# design.net
KiCad netlist of a schematic drawn in EasyEDA Pro
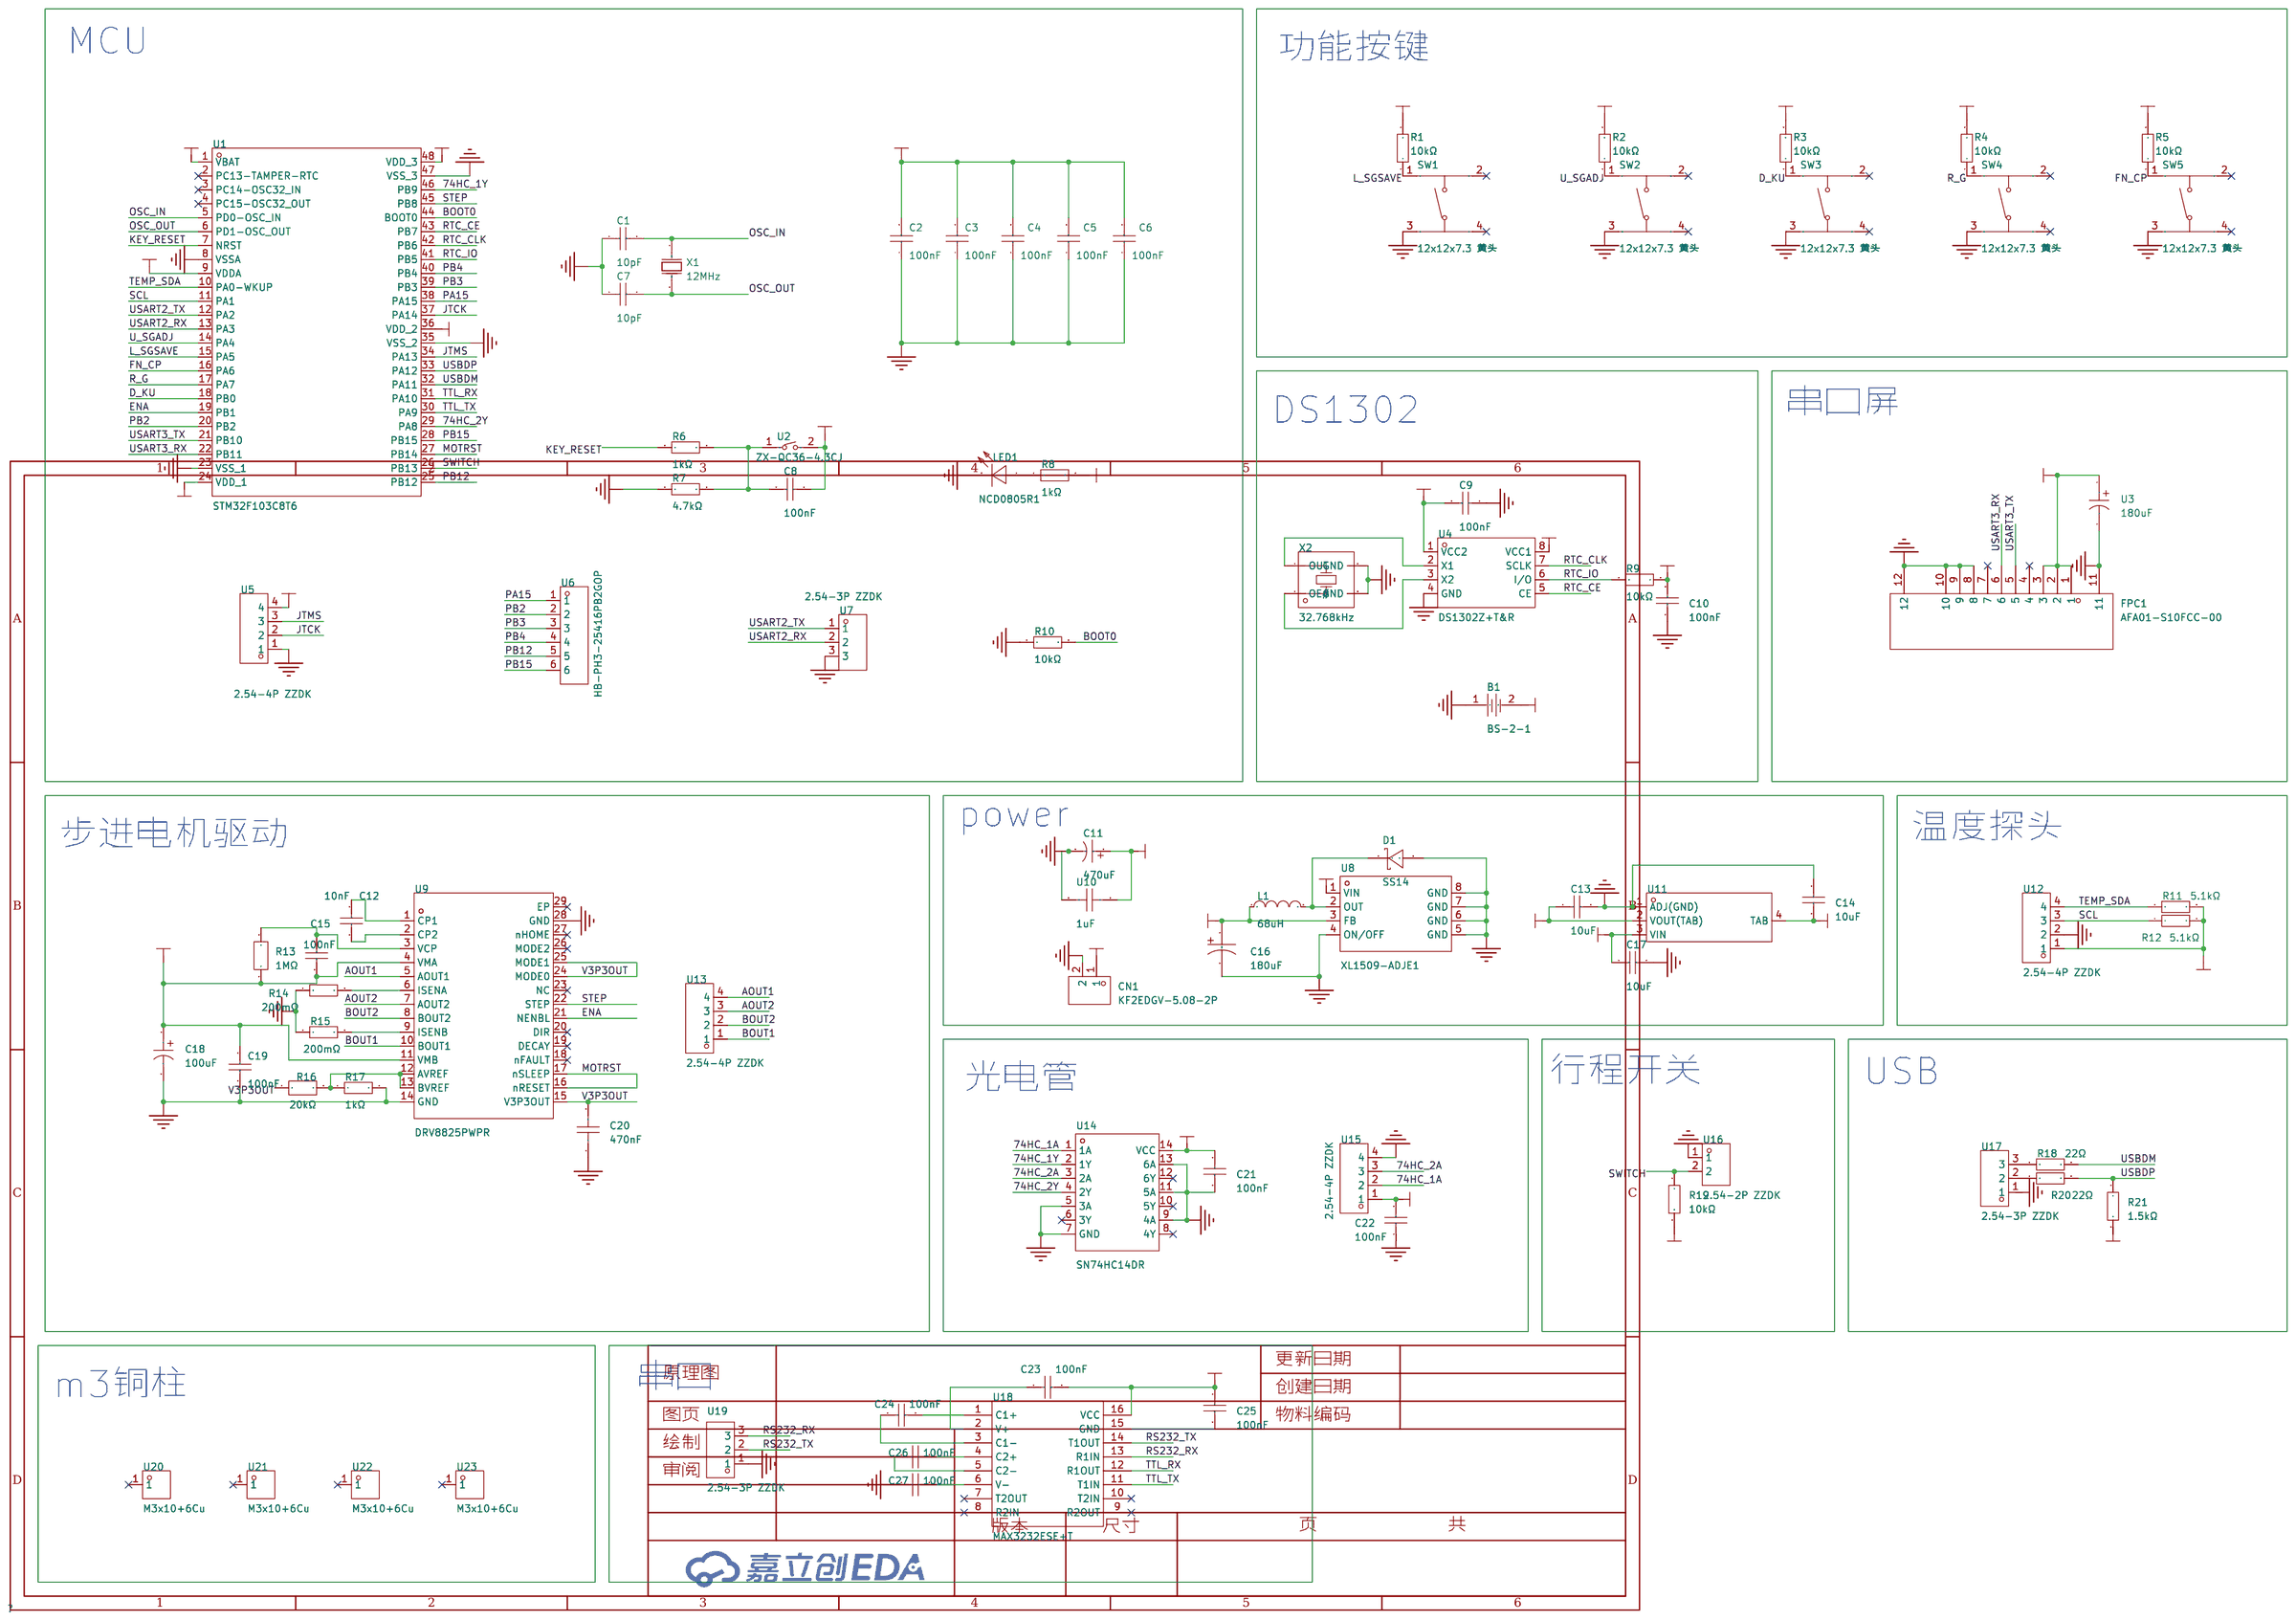
[diagram p0: schematic sheet]

(export (version "E")
  (design (tool "Eeschema 10.0.6"))
  (components
    (comp (ref "B1")
      (value "BS-2-1")
      (footprint "easyedapro:BAT-TH_BS-2-1")
      (description "连接器类型:电池底座;适用电池规格:-;工作温度范围:-55°C~+85°C;")
      (fields (field (name "Manufacturer") "Q&J"))
      (libsource (lib "easyedapro") (part "CR2032-BS-2-1"))
    )
    (comp (ref "C1")
      (value "10pF")
      (footprint "easyedapro:C0603")
      (description "容值:10pF;精度:±5%;额定电压:50V;材质(温度系数):C0G;")
      (fields
        (field (name "Manufacturer Part") "CL10C100JB8NNNC")
        (field (name "Manufacturer") "SAMSUNG(三星)")
      )
      (libsource (lib "easyedapro") (part "CL10C100JB8NNNC"))
    )
    (comp (ref "C2")
      (value "100nF")
      (footprint "easyedapro:C0805")
      (description "容值:100nF;精度:±10%;额定电压:50V;材质(温度系数):X7R;")
      (fields
        (field (name "Manufacturer Part") "CL21B104KBCNNNC")
        (field (name "Manufacturer") "SAMSUNG(三星)")
      )
      (libsource (lib "easyedapro") (part "CL21B104KBCNNNC"))
    )
    (comp (ref "C3")
      (value "100nF")
      (footprint "easyedapro:C0805")
      (description "容值:100nF;精度:±10%;额定电压:50V;材质(温度系数):X7R;")
      (fields
        (field (name "Manufacturer Part") "CL21B104KBCNNNC")
        (field (name "Manufacturer") "SAMSUNG(三星)")
      )
      (libsource (lib "easyedapro") (part "CL21B104KBCNNNC"))
    )
    (comp (ref "C4")
      (value "100nF")
      (footprint "easyedapro:C0805")
      (description "容值:100nF;精度:±10%;额定电压:50V;材质(温度系数):X7R;")
      (fields
        (field (name "Manufacturer Part") "CL21B104KBCNNNC")
        (field (name "Manufacturer") "SAMSUNG(三星)")
      )
      (libsource (lib "easyedapro") (part "CL21B104KBCNNNC"))
    )
    (comp (ref "C5")
      (value "100nF")
      (footprint "easyedapro:C0805")
      (description "容值:100nF;精度:±10%;额定电压:50V;材质(温度系数):X7R;")
      (fields
        (field (name "Manufacturer Part") "CL21B104KBCNNNC")
        (field (name "Manufacturer") "SAMSUNG(三星)")
      )
      (libsource (lib "easyedapro") (part "CL21B104KBCNNNC"))
    )
    (comp (ref "C6")
      (value "100nF")
      (footprint "easyedapro:C0805")
      (description "容值:100nF;精度:±10%;额定电压:50V;材质(温度系数):X7R;")
      (fields
        (field (name "Manufacturer Part") "CL21B104KBCNNNC")
        (field (name "Manufacturer") "SAMSUNG(三星)")
      )
      (libsource (lib "easyedapro") (part "CL21B104KBCNNNC"))
    )
    (comp (ref "C7")
      (value "10pF")
      (footprint "easyedapro:C0603")
      (description "容值:10pF;精度:±5%;额定电压:50V;材质(温度系数):C0G;")
      (fields
        (field (name "Manufacturer Part") "CL10C100JB8NNNC")
        (field (name "Manufacturer") "SAMSUNG(三星)")
      )
      (libsource (lib "easyedapro") (part "CL10C100JB8NNNC"))
    )
    (comp (ref "C8")
      (value "100nF")
      (footprint "easyedapro:C0805")
      (description "容值:100nF;精度:±10%;额定电压:50V;材质(温度系数):X7R;")
      (fields
        (field (name "Manufacturer Part") "CL21B104KBCNNNC")
        (field (name "Manufacturer") "SAMSUNG(三星)")
      )
      (libsource (lib "easyedapro") (part "CL21B104KBCNNNC"))
    )
    (comp (ref "C9")
      (value "100nF")
      (footprint "easyedapro:C0805")
      (description "容值:100nF;精度:±10%;额定电压:50V;材质(温度系数):X7R;")
      (fields
        (field (name "Manufacturer Part") "CL21B104KBCNNNC")
        (field (name "Manufacturer") "SAMSUNG(三星)")
      )
      (libsource (lib "easyedapro") (part "CL21B104KBCNNNC"))
    )
    (comp (ref "C10")
      (value "100nF")
      (footprint "easyedapro:C0805")
      (description "容值:100nF;精度:±10%;额定电压:50V;材质(温度系数):X7R;")
      (fields
        (field (name "Manufacturer Part") "CL21B104KBCNNNC")
        (field (name "Manufacturer") "SAMSUNG(三星)")
      )
      (libsource (lib "easyedapro") (part "CL21B104KBCNNNC"))
    )
    (comp (ref "C11")
      (value "470uF")
      (footprint "easyedapro:CAP-SMD_BD10.0-L10.3-W10.3-LS11.0-R-RD")
      (description "容值:470uF;精度:±20%;额定电压:35V;纹波电流:286mA@120Hz;等效串联电阻:-;")
      (fields (field (name "Manufacturer Part") "RVT1V471M1010") (field (name "Manufacturer") "ROQANG(容强)"))
      (libsource (lib "easyedapro") (part "RVT1V471M1010-C72519"))
    )
    (comp (ref "C12")
      (value "10nF")
      (footprint "easyedapro:C0805")
      (description "容值:10nF;精度:±10%;额定电压:50V;材质(温度系数):X7R;")
      (fields
        (field (name "Manufacturer Part") "CL21B103KBANNNC")
        (field (name "Manufacturer") "SAMSUNG(三星)")
      )
      (libsource (lib "easyedapro") (part "CL21B103KBANNNC"))
    )
    (comp (ref "C13")
      (value "10uF")
      (footprint "easyedapro:C0805")
      (description "容值:10uF;精度:±10%;额定电压:16V;材质(温度系数):X5R;")
      (fields
        (field (name "Manufacturer Part") "CL21A106KOQNNNE")
        (field (name "Manufacturer") "SAMSUNG(三星)")
      )
      (libsource (lib "easyedapro") (part "CL21A106KOQNNNE"))
    )
    (comp (ref "C14")
      (value "10uF")
      (footprint "easyedapro:C0805")
      (description "容值:10uF;精度:±10%;额定电压:16V;材质(温度系数):X5R;")
      (fields
        (field (name "Manufacturer Part") "CL21A106KOQNNNE")
        (field (name "Manufacturer") "SAMSUNG(三星)")
      )
      (libsource (lib "easyedapro") (part "CL21A106KOQNNNE"))
    )
    (comp (ref "C15")
      (value "100nF")
      (footprint "easyedapro:C0805")
      (description "容值:100nF;精度:±10%;额定电压:50V;材质(温度系数):X7R;")
      (fields
        (field (name "Manufacturer Part") "CL21B104KBCNNNC")
        (field (name "Manufacturer") "SAMSUNG(三星)")
      )
      (libsource (lib "easyedapro") (part "CL21B104KBCNNNC"))
    )
    (comp (ref "C16")
      (value "180uF")
      (footprint "easyedapro:CAP-TH_BD8.0-P3.50-D0.6-FD")
      (description "容值:180uF;精度:±20%;额定电压:35V;纹波电流:900mA@100kHz;等效串联电阻:210mΩ@100kHz;")
      (fields (field (name "Manufacturer Part") "LKMD0901V181MF") (field (name "Manufacturer") "Ymin(永铭)"))
      (libsource (lib "easyedapro") (part "LKMD0901V181MF"))
    )
    (comp (ref "C17")
      (value "10uF")
      (footprint "easyedapro:C0805")
      (description "容值:10uF;精度:±10%;额定电压:16V;材质(温度系数):X5R;")
      (fields
        (field (name "Manufacturer Part") "CL21A106KOQNNNE")
        (field (name "Manufacturer") "SAMSUNG(三星)")
      )
      (libsource (lib "easyedapro") (part "CL21A106KOQNNNE"))
    )
    (comp (ref "C18")
      (value "100uF")
      (footprint "easyedapro:CAP-SMD_BD6.3-L6.6-W6.6-LS7.6-FD-1")
      (description "容值:100uF;精度:±20%;额定电压:35V;纹波电流:230mA@120Hz;等效串联电阻:600mΩ@100kHz;")
      (fields
        (field (name "Manufacturer Part") "RVE100UF35V67RV0072")
        (field (name "Manufacturer") "KNSCHA(科尼盛)")
      )
      (libsource (lib "easyedapro") (part "RVE100UF35V67RV0072"))
    )
    (comp (ref "C19")
      (value "100nF")
      (footprint "easyedapro:C0805")
      (description "容值:100nF;精度:±10%;额定电压:50V;材质(温度系数):X7R;")
      (fields
        (field (name "Manufacturer Part") "CL21B104KBCNNNC")
        (field (name "Manufacturer") "SAMSUNG(三星)")
      )
      (libsource (lib "easyedapro") (part "CL21B104KBCNNNC"))
    )
    (comp (ref "C20")
      (value "470nF")
      (footprint "easyedapro:CAP-TH_L18.0-W8.5-P15.00-D0.8")
      (description "容值:470nF;精度:±10%;电压(AC):275V；310V；305V;等级:X2;")
      (fields
        (field (name "Manufacturer Part") "MPX474K31D4KN15800")
        (field (name "Manufacturer") "KNSCHA(科尼盛)")
      )
      (libsource (lib "easyedapro") (part "MPX474K31D4KN15800"))
    )
    (comp (ref "C21")
      (value "100nF")
      (footprint "easyedapro:C0805")
      (description "容值:100nF;精度:±10%;额定电压:50V;材质(温度系数):X7R;")
      (fields
        (field (name "Manufacturer Part") "CL21B104KBCNNNC")
        (field (name "Manufacturer") "SAMSUNG(三星)")
      )
      (libsource (lib "easyedapro") (part "CL21B104KBCNNNC"))
    )
    (comp (ref "C22")
      (value "100nF")
      (footprint "easyedapro:C0805")
      (description "容值:100nF;精度:±10%;额定电压:50V;材质(温度系数):X7R;")
      (fields
        (field (name "Manufacturer Part") "CL21B104KBCNNNC")
        (field (name "Manufacturer") "SAMSUNG(三星)")
      )
      (libsource (lib "easyedapro") (part "CL21B104KBCNNNC"))
    )
    (comp (ref "C23")
      (value "100nF")
      (footprint "easyedapro:C0805")
      (description "容值:100nF;精度:±10%;额定电压:50V;材质(温度系数):X7R;")
      (fields
        (field (name "Manufacturer Part") "CL21B104KBCNNNC")
        (field (name "Manufacturer") "SAMSUNG(三星)")
      )
      (libsource (lib "easyedapro") (part "CL21B104KBCNNNC"))
    )
    (comp (ref "C24")
      (value "100nF")
      (footprint "easyedapro:C0805")
      (description "容值:100nF;精度:±10%;额定电压:50V;材质(温度系数):X7R;")
      (fields
        (field (name "Manufacturer Part") "CL21B104KBCNNNC")
        (field (name "Manufacturer") "SAMSUNG(三星)")
      )
      (libsource (lib "easyedapro") (part "CL21B104KBCNNNC"))
    )
    (comp (ref "C25")
      (value "100nF")
      (footprint "easyedapro:C0805")
      (description "容值:100nF;精度:±10%;额定电压:50V;材质(温度系数):X7R;")
      (fields
        (field (name "Manufacturer Part") "CL21B104KBCNNNC")
        (field (name "Manufacturer") "SAMSUNG(三星)")
      )
      (libsource (lib "easyedapro") (part "CL21B104KBCNNNC"))
    )
    (comp (ref "C26")
      (value "100nF")
      (footprint "easyedapro:C0805")
      (description "容值:100nF;精度:±10%;额定电压:50V;材质(温度系数):X7R;")
      (fields
        (field (name "Manufacturer Part") "CL21B104KBCNNNC")
        (field (name "Manufacturer") "SAMSUNG(三星)")
      )
      (libsource (lib "easyedapro") (part "CL21B104KBCNNNC"))
    )
    (comp (ref "C27")
      (value "100nF")
      (footprint "easyedapro:C0805")
      (description "容值:100nF;精度:±10%;额定电压:50V;材质(温度系数):X7R;")
      (fields
        (field (name "Manufacturer Part") "CL21B104KBCNNNC")
        (field (name "Manufacturer") "SAMSUNG(三星)")
      )
      (libsource (lib "easyedapro") (part "CL21B104KBCNNNC"))
    )
    (comp (ref "CN1")
      (value "KF2EDGV-5.08-2P")
      (footprint "easyedapro:CONN-TH_P5.08_KF2EDGV-5.08-2P")
      (fields (field (name "Manufacturer") "KEFA(科发)"))
      (libsource (lib "easyedapro") (part "KF2EDGV-5.08-2P"))
    )
    (comp (ref "D1")
      (value "SS14")
      (footprint "easyedapro:SMA_L4.2-W2.6-LS5.3-RD")
      (description "二极管配置:独立式;正向压降(Vf):550mV@1A;直流反向耐压(Vr):40V;整流电流:1A;")
      (fields (field (name "Manufacturer") "MDD(辰达半导体)"))
      (libsource (lib "easyedapro") (part "SS14"))
    )
    (comp (ref "FPC1")
      (value "AFA01-S10FCC-00")
      (footprint "easyedapro:FPC-SMD_AFA01-S10FCC-00")
      (description "锁定特性:翻盖式;触点类型:下接;触点数量:10P;间距:1mm;安装类型:卧贴;")
      (fields (field (name "Manufacturer") "JS(钜硕电子)"))
      (libsource (lib "easyedapro") (part "AFA01-S10FCC-00"))
    )
    (comp (ref "L1")
      (value "68uH")
      (footprint "easyedapro:IND-SMD_L8.0-W8.0_SMNR8040")
      (description "电感值:68uH;精度:±20%;额定电流:1.25A;饱和电流(Isat):1.45A;类型:-;")
      (fields (field (name "Manufacturer Part") "SWPA8040S680MT") (field (name "Manufacturer") "Sunlord(顺络)"))
      (libsource (lib "easyedapro") (part "SWPA8040S680MT"))
    )
    (comp (ref "LED1")
      (value "NCD0805R1")
      (footprint "easyedapro:LED0805-R-RD")
      (fields (field (name "Manufacturer") "国星光电"))
      (libsource (lib "easyedapro") (part "FC-2012HRK-620D"))
    )
    (comp (ref "R1")
      (value "10kΩ")
      (footprint "easyedapro:R0805")
      (description "电阻类型:厚膜电阻;阻值:10kΩ;精度:±1%;功率:125mW;最大工作电压:150V;温度系数:±100ppm/°C;")
      (fields
        (field (name "Manufacturer Part") "0805W8F1002T5E")
        (field (name "Manufacturer") "UNI-ROYAL(厚声)")
      )
      (libsource (lib "easyedapro") (part "0805W8F1002T5E"))
    )
    (comp (ref "R2")
      (value "10kΩ")
      (footprint "easyedapro:R0805")
      (description "电阻类型:厚膜电阻;阻值:10kΩ;精度:±1%;功率:125mW;最大工作电压:150V;温度系数:±100ppm/°C;")
      (fields
        (field (name "Manufacturer Part") "0805W8F1002T5E")
        (field (name "Manufacturer") "UNI-ROYAL(厚声)")
      )
      (libsource (lib "easyedapro") (part "0805W8F1002T5E"))
    )
    (comp (ref "R3")
      (value "10kΩ")
      (footprint "easyedapro:R0805")
      (description "电阻类型:厚膜电阻;阻值:10kΩ;精度:±1%;功率:125mW;最大工作电压:150V;温度系数:±100ppm/°C;")
      (fields
        (field (name "Manufacturer Part") "0805W8F1002T5E")
        (field (name "Manufacturer") "UNI-ROYAL(厚声)")
      )
      (libsource (lib "easyedapro") (part "0805W8F1002T5E"))
    )
    (comp (ref "R4")
      (value "10kΩ")
      (footprint "easyedapro:R0805")
      (description "电阻类型:厚膜电阻;阻值:10kΩ;精度:±1%;功率:125mW;最大工作电压:150V;温度系数:±100ppm/°C;")
      (fields
        (field (name "Manufacturer Part") "0805W8F1002T5E")
        (field (name "Manufacturer") "UNI-ROYAL(厚声)")
      )
      (libsource (lib "easyedapro") (part "0805W8F1002T5E"))
    )
    (comp (ref "R5")
      (value "10kΩ")
      (footprint "easyedapro:R0805")
      (description "电阻类型:厚膜电阻;阻值:10kΩ;精度:±1%;功率:125mW;最大工作电压:150V;温度系数:±100ppm/°C;")
      (fields
        (field (name "Manufacturer Part") "0805W8F1002T5E")
        (field (name "Manufacturer") "UNI-ROYAL(厚声)")
      )
      (libsource (lib "easyedapro") (part "0805W8F1002T5E"))
    )
    (comp (ref "R6")
      (value "1kΩ")
      (footprint "easyedapro:R0805")
      (description "电阻类型:厚膜电阻;阻值:1kΩ;精度:±1%;功率:125mW;最大工作电压:150V;温度系数:±100ppm/°C;")
      (fields
        (field (name "Manufacturer Part") "0805W8F1001T5E")
        (field (name "Manufacturer") "UNI-ROYAL(厚声)")
      )
      (libsource (lib "easyedapro") (part "0805W8F1001T5E"))
    )
    (comp (ref "R7")
      (value "4.7kΩ")
      (footprint "easyedapro:R0805")
      (description "电阻类型:厚膜电阻;阻值:4.7kΩ;精度:±1%;功率:125mW;最大工作电压:150V;温度系数:±100ppm/°C;")
      (fields
        (field (name "Manufacturer Part") "0805W8F4701T5E")
        (field (name "Manufacturer") "UNI-ROYAL(厚声)")
      )
      (libsource (lib "easyedapro") (part "0805W8F4701T5E"))
    )
    (comp (ref "R8")
      (value "1kΩ")
      (footprint "easyedapro:R0805")
      (description "电阻类型:厚膜电阻;阻值:1kΩ;精度:±1%;功率:125mW;最大工作电压:150V;温度系数:±100ppm/°C;")
      (fields
        (field (name "Manufacturer Part") "0805W8F1001T5E")
        (field (name "Manufacturer") "UNI-ROYAL(厚声)")
      )
      (libsource (lib "easyedapro") (part "0805W8F1001T5E"))
    )
    (comp (ref "R9")
      (value "10kΩ")
      (footprint "easyedapro:R0805")
      (description "电阻类型:厚膜电阻;阻值:10kΩ;精度:±1%;功率:125mW;最大工作电压:150V;温度系数:±100ppm/°C;")
      (fields
        (field (name "Manufacturer Part") "0805W8F1002T5E")
        (field (name "Manufacturer") "UNI-ROYAL(厚声)")
      )
      (libsource (lib "easyedapro") (part "0805W8F1002T5E"))
    )
    (comp (ref "R10")
      (value "10kΩ")
      (footprint "easyedapro:R0805")
      (description "电阻类型:厚膜电阻;阻值:10kΩ;精度:±1%;功率:125mW;最大工作电压:150V;温度系数:±100ppm/°C;")
      (fields
        (field (name "Manufacturer Part") "0805W8F1002T5E")
        (field (name "Manufacturer") "UNI-ROYAL(厚声)")
      )
      (libsource (lib "easyedapro") (part "0805W8F1002T5E"))
    )
    (comp (ref "R11")
      (value "5.1kΩ")
      (footprint "easyedapro:R0805")
      (description "电阻类型:厚膜电阻;阻值:5.1kΩ;精度:±1%;功率:125mW;最大工作电压:150V;温度系数:±100ppm/°C;")
      (fields
        (field (name "Manufacturer Part") "0805W8F5101T5E")
        (field (name "Manufacturer") "UNI-ROYAL(厚声)")
      )
      (libsource (lib "easyedapro") (part "0805W8F5101T5E"))
    )
    (comp (ref "R12")
      (value "5.1kΩ")
      (footprint "easyedapro:R0805")
      (description "电阻类型:厚膜电阻;阻值:5.1kΩ;精度:±1%;功率:125mW;最大工作电压:150V;温度系数:±100ppm/°C;")
      (fields
        (field (name "Manufacturer Part") "0805W8F5101T5E")
        (field (name "Manufacturer") "UNI-ROYAL(厚声)")
      )
      (libsource (lib "easyedapro") (part "0805W8F5101T5E"))
    )
    (comp (ref "R13")
      (value "1MΩ")
      (footprint "easyedapro:R0805")
      (description "阻值:1MΩ;精度:±1%;功率:-;温度系数:±100ppm/°C;")
      (fields
        (field (name "Manufacturer Part") "SC0805F1004F4ANRH")
        (field (name "Manufacturer") "Sunway(信维通信)")
      )
      (libsource (lib "easyedapro") (part "SC0805F1004F4ANRH"))
    )
    (comp (ref "R14")
      (value "200mΩ")
      (footprint "easyedapro:R2512")
      (description "电阻类型:厚膜电阻;阻值:200mΩ;精度:±1%;功率:1W;最大工作电压:200V;温度系数:±800ppm/°C;")
      (fields
        (field (name "Manufacturer Part") "25121WF200LT4E")
        (field (name "Manufacturer") "UNI-ROYAL(厚声)")
      )
      (libsource (lib "easyedapro") (part "25121WF200LT4E"))
    )
    (comp (ref "R15")
      (value "200mΩ")
      (footprint "easyedapro:R2512")
      (description "电阻类型:厚膜电阻;阻值:200mΩ;精度:±1%;功率:1W;最大工作电压:200V;温度系数:±800ppm/°C;")
      (fields
        (field (name "Manufacturer Part") "25121WF200LT4E")
        (field (name "Manufacturer") "UNI-ROYAL(厚声)")
      )
      (libsource (lib "easyedapro") (part "25121WF200LT4E"))
    )
    (comp (ref "R16")
      (value "20kΩ")
      (footprint "easyedapro:R0805")
      (description "电阻类型:厚膜电阻;阻值:20kΩ;精度:±1%;功率:125mW;最大工作电压:150V;温度系数:±100ppm/°C;")
      (fields (field (name "Manufacturer Part") "FRC0805F2002TS") (field (name "Manufacturer") "FOJAN(富捷)"))
      (libsource (lib "easyedapro") (part "FRC0805F2002TS"))
    )
    (comp (ref "R17")
      (value "1kΩ")
      (footprint "easyedapro:R0805")
      (description "电阻类型:厚膜电阻;阻值:1kΩ;精度:±1%;功率:125mW;最大工作电压:150V;温度系数:±100ppm/°C;")
      (fields
        (field (name "Manufacturer Part") "0805W8F1001T5E")
        (field (name "Manufacturer") "UNI-ROYAL(厚声)")
      )
      (libsource (lib "easyedapro") (part "0805W8F1001T5E"))
    )
    (comp (ref "R18")
      (value "22Ω")
      (footprint "easyedapro:R0805")
      (description "电阻类型:厚膜电阻;阻值:22Ω;精度:±1%;功率:125mW;最大工作电压:150V;温度系数:±100ppm/°C;")
      (fields
        (field (name "Manufacturer Part") "0805W8F220JT5E")
        (field (name "Manufacturer") "UNI-ROYAL(厚声)")
      )
      (libsource (lib "easyedapro") (part "0805W8F220JT5E"))
    )
    (comp (ref "R19")
      (value "10kΩ")
      (footprint "easyedapro:R0805")
      (description "电阻类型:厚膜电阻;阻值:10kΩ;精度:±1%;功率:125mW;最大工作电压:150V;温度系数:±100ppm/°C;")
      (fields
        (field (name "Manufacturer Part") "0805W8F1002T5E")
        (field (name "Manufacturer") "UNI-ROYAL(厚声)")
      )
      (libsource (lib "easyedapro") (part "0805W8F1002T5E"))
    )
    (comp (ref "R20")
      (value "22Ω")
      (footprint "easyedapro:R0805")
      (description "电阻类型:厚膜电阻;阻值:22Ω;精度:±1%;功率:125mW;最大工作电压:150V;温度系数:±100ppm/°C;")
      (fields
        (field (name "Manufacturer Part") "0805W8F220JT5E")
        (field (name "Manufacturer") "UNI-ROYAL(厚声)")
      )
      (libsource (lib "easyedapro") (part "0805W8F220JT5E"))
    )
    (comp (ref "R21")
      (value "1.5kΩ")
      (footprint "easyedapro:R0603")
      (description "电阻类型:厚膜电阻;阻值:1.5kΩ;精度:±1%;功率:100mW;最大工作电压:75V;温度系数:±100ppm/°C;")
      (fields
        (field (name "Manufacturer Part") "0603WAF1501T5E")
        (field (name "Manufacturer") "UNI-ROYAL(厚声)")
      )
      (libsource (lib "easyedapro") (part "0603WAF1501T5E"))
    )
    (comp (ref "SW1")
      (value "12x12x7.3 黄头")
      (footprint "easyedapro:SW-TH_4P-L12.0-W12.0-P5.00-LS12.5")
      (description "电路结构:单刀单掷;按钮形状:矩形按钮;安装方式:直插;开关长度:12mm;开关宽度:12mm;开关高度:7.3mm;触点电流:50mA;额定电压(DC):12V;带灯:-;机械寿命:-;")
      (fields (field (name "Manufacturer") "BOOMELE(博穆精密)"))
      (libsource (lib "easyedapro") (part "12X12X7.3"))
    )
    (comp (ref "SW2")
      (value "12x12x7.3 黄头")
      (footprint "easyedapro:SW-TH_4P-L12.0-W12.0-P5.00-LS12.5")
      (description "电路结构:单刀单掷;按钮形状:矩形按钮;安装方式:直插;开关长度:12mm;开关宽度:12mm;开关高度:7.3mm;触点电流:50mA;额定电压(DC):12V;带灯:-;机械寿命:-;")
      (fields (field (name "Manufacturer") "BOOMELE(博穆精密)"))
      (libsource (lib "easyedapro") (part "12X12X7.3"))
    )
    (comp (ref "SW3")
      (value "12x12x7.3 黄头")
      (footprint "easyedapro:SW-TH_4P-L12.0-W12.0-P5.00-LS12.5")
      (description "电路结构:单刀单掷;按钮形状:矩形按钮;安装方式:直插;开关长度:12mm;开关宽度:12mm;开关高度:7.3mm;触点电流:50mA;额定电压(DC):12V;带灯:-;机械寿命:-;")
      (fields (field (name "Manufacturer") "BOOMELE(博穆精密)"))
      (libsource (lib "easyedapro") (part "12X12X7.3"))
    )
    (comp (ref "SW4")
      (value "12x12x7.3 黄头")
      (footprint "easyedapro:SW-TH_4P-L12.0-W12.0-P5.00-LS12.5")
      (description "电路结构:单刀单掷;按钮形状:矩形按钮;安装方式:直插;开关长度:12mm;开关宽度:12mm;开关高度:7.3mm;触点电流:50mA;额定电压(DC):12V;带灯:-;机械寿命:-;")
      (fields (field (name "Manufacturer") "BOOMELE(博穆精密)"))
      (libsource (lib "easyedapro") (part "12X12X7.3"))
    )
    (comp (ref "SW5")
      (value "12x12x7.3 黄头")
      (footprint "easyedapro:SW-TH_4P-L12.0-W12.0-P5.00-LS12.5")
      (description "电路结构:单刀单掷;按钮形状:矩形按钮;安装方式:直插;开关长度:12mm;开关宽度:12mm;开关高度:7.3mm;触点电流:50mA;额定电压(DC):12V;带灯:-;机械寿命:-;")
      (fields (field (name "Manufacturer") "BOOMELE(博穆精密)"))
      (libsource (lib "easyedapro") (part "12X12X7.3"))
    )
    (comp (ref "U1")
      (value "STM32F103C8T6")
      (footprint "easyedapro:LQFP-48_L7.0-W7.0-P0.50-LS9.0-BL")
      (description "CPU内核:ARM-M3;CPU最大主频:72MHz;应用领域:-;")
      (fields (field (name "Manufacturer") "ST(意法半导体)"))
      (libsource (lib "easyedapro") (part "STM32F103C8T6"))
    )
    (comp (ref "U2")
      (value "ZX-QC36-4.3CJ")
      (footprint "easyedapro:KEY-TH_L6.0-W3.5-P6.50")
      (fields (field (name "Manufacturer") "Megastar(兆星)"))
      (libsource (lib "easyedapro") (part "ZX-QC36-4.3CJ"))
    )
    (comp (ref "U3")
      (value "180uF")
      (footprint "easyedapro:CAP-SMD_BD6.3-L6.6-W6.6-LS7.3-FD")
      (description "容值:180uF;精度:±20%;额定电压:16V;纹波电流:3.3A@100kHz;等效串联电阻:22mΩ@100kHz;")
      (fields
        (field (name "Manufacturer Part") "KNM2180UF16V118EC0094")
        (field (name "Manufacturer") "KNSCHA(科尼盛)")
      )
      (libsource (lib "easyedapro") (part "KNM2180UF16V118EC0094"))
    )
    (comp (ref "U4")
      (value "DS1302Z+T&R")
      (footprint "easyedapro:SOIC-8_L4.9-W3.9-P1.27-LS6.0-BL")
      (description "接口:SPI;")
      (fields (field (name "Manufacturer") "ADI(亚德诺)/MAXIM(美信)"))
      (libsource (lib "easyedapro") (part "DS1302ZN+"))
    )
    (comp (ref "U5")
      (value "2.54-4P ZZDK")
      (footprint "easyedapro:HDR-TH_4P-P2.50-V-F-2")
      (fields (field (name "Manufacturer") "SHOU HAN(首韩)"))
      (libsource (lib "easyedapro") (part "2.54-4P ZZDK"))
    )
    (comp (ref "U6")
      (value "HB-PH3-25416PB2GOP")
      (footprint "easyedapro:HDR-TH_6P-P2.54-V-M")
      (fields (field (name "Manufacturer") "HANBO(汉博)"))
      (libsource (lib "easyedapro") (part "HB-PH3-25416PB2GOP"))
    )
    (comp (ref "U7")
      (value "2.54-3P ZZDK")
      (footprint "easyedapro:HDR-TH_3P-P2.50-V-F-2")
      (fields (field (name "Manufacturer") "SHOU HAN(首韩)"))
      (libsource (lib "easyedapro") (part "2.54-3P ZZDK"))
    )
    (comp (ref "U8")
      (value "XL1509-ADJE1")
      (footprint "easyedapro:SOIC-8_L5.0-W4.0-P1.27-LS6.0-BL")
      (description "功能类型:降压型;输入电压:-;输出电流(最大值):-;")
      (fields (field (name "Manufacturer") "XLSEMI(芯龙)"))
      (libsource (lib "easyedapro") (part "XL1509-ADJE1"))
    )
    (comp (ref "U9")
      (value "DRV8825PWPR")
      (footprint "easyedapro:HTSSOP-28_L9.7-W4.4-P0.65-LS6.4-BL-EP")
      (description "DRV8825 具有电流调节功能和 1/32 微步进的 45V、2.5A 双极步进电机驱动器")
      (fields (field (name "Manufacturer") "TI(德州仪器)"))
      (libsource (lib "easyedapro") (part "DRV8825PWPR"))
    )
    (comp (ref "U10")
      (value "1uF")
      (footprint "easyedapro:C1210")
      (description "容值:1uF;精度:±20%;额定电压:16V；12V;介电材料:丙烯酸;工作温度:-40°C~+85°C;")
      (fields (field (name "Manufacturer Part") "ECPU1C105MA5") (field (name "Manufacturer") "PANASONIC(松下)"))
      (libsource (lib "easyedapro") (part "ECPU1C105MA5"))
    )
    (comp (ref "U11")
      (value "AMS1117-3.3")
      (footprint "easyedapro:SOT-223-4_L6.5-W3.5-P2.30-LS7.0-BR")
      (description "输出类型:固定;工作电压:12V;输出电压:3.3V;输出电流:1A;电源纹波抑制比(PSRR):60dB@(120Hz);输出极性:正极;")
      (fields (field (name "Manufacturer") "UMW(友台半导体)"))
      (libsource (lib "easyedapro") (part "AMS1117-3.3_C347222"))
    )
    (comp (ref "U12")
      (value "2.54-4P ZZDK")
      (footprint "easyedapro:HDR-TH_4P-P2.50-V-F-2")
      (fields (field (name "Manufacturer") "SHOU HAN(首韩)"))
      (libsource (lib "easyedapro") (part "2.54-4P ZZDK"))
    )
    (comp (ref "U13")
      (value "2.54-4P ZZDK")
      (footprint "easyedapro:HDR-TH_4P-P2.50-V-F-2")
      (fields (field (name "Manufacturer") "SHOU HAN(首韩)"))
      (libsource (lib "easyedapro") (part "2.54-4P ZZDK"))
    )
    (comp (ref "U14")
      (value "SN74HC14DR")
      (footprint "easyedapro:SOIC-14_L8.7-W3.9-P1.27-LS6.0-BL")
      (description "输入类型:施密特触发器;电源电压:2V~6V;供电电流(最大值):2uA;电路数:6;最大传播延迟(tpd):21ns@6V,50pF;")
      (fields (field (name "Manufacturer") "TI(德州仪器)"))
      (libsource (lib "easyedapro") (part "SN74HC14DR"))
    )
    (comp (ref "U15")
      (value "2.54-4P ZZDK")
      (footprint "easyedapro:HDR-TH_4P-P2.50-V-F-2")
      (fields (field (name "Manufacturer") "SHOU HAN(首韩)"))
      (libsource (lib "easyedapro") (part "2.54-4P ZZDK"))
    )
    (comp (ref "U16")
      (value "2.54-2P ZZDK")
      (footprint "easyedapro:HDR-TH_2P-P2.50-V-F-1")
      (fields (field (name "Manufacturer") "SHOU HAN(首韩)"))
      (libsource (lib "easyedapro") (part "2.54-2P ZZDK"))
    )
    (comp (ref "U17")
      (value "2.54-3P ZZDK")
      (footprint "easyedapro:HDR-TH_3P-P2.50-V-F-2")
      (fields (field (name "Manufacturer") "SHOU HAN(首韩)"))
      (libsource (lib "easyedapro") (part "2.54-3P ZZDK"))
    )
    (comp (ref "U18")
      (value "MAX3232ESE+T")
      (footprint "easyedapro:SOIC-16_L9.9-W3.9-P1.27-LS6.0-BL")
      (description "类型:收发器;数据速率:250Kbps;")
      (fields (field (name "Manufacturer") "ADI(亚德诺)/MAXIM(美信)"))
      (libsource (lib "easyedapro") (part "MAX3232ESE+T"))
    )
    (comp (ref "U19")
      (value "2.54-3P ZZDK")
      (footprint "easyedapro:HDR-TH_3P-P2.50-V-F-2")
      (fields (field (name "Manufacturer") "SHOU HAN(首韩)"))
      (libsource (lib "easyedapro") (part "2.54-3P ZZDK"))
    )
    (comp (ref "U20")
      (value "M3x10+6Cu")
      (footprint "easyedapro:SMD_L4.7-W4.7-D3.0")
      (description "M3x10+6")
      (fields (field (name "Manufacturer") "Shuntian(顺天五金)"))
      (libsource (lib "easyedapro") (part "M3X10+6CU"))
    )
    (comp (ref "U21")
      (value "M3x10+6Cu")
      (footprint "easyedapro:SMD_L4.7-W4.7-D3.0")
      (description "M3x10+6")
      (fields (field (name "Manufacturer") "Shuntian(顺天五金)"))
      (libsource (lib "easyedapro") (part "M3X10+6CU"))
    )
    (comp (ref "U22")
      (value "M3x10+6Cu")
      (footprint "easyedapro:SMD_L4.7-W4.7-D3.0")
      (description "M3x10+6")
      (fields (field (name "Manufacturer") "Shuntian(顺天五金)"))
      (libsource (lib "easyedapro") (part "M3X10+6CU"))
    )
    (comp (ref "U23")
      (value "M3x10+6Cu")
      (footprint "easyedapro:SMD_L4.7-W4.7-D3.0")
      (description "M3x10+6")
      (fields (field (name "Manufacturer") "Shuntian(顺天五金)"))
      (libsource (lib "easyedapro") (part "M3X10+6CU"))
    )
    (comp (ref "X1")
      (value "12MHz")
      (footprint "easyedapro:OSC-SMD_L5.0-W3.2")
      (description "晶振类型:贴片晶振;频率:12MHz;常温频差:±30ppm;外接负载电容:20pF;频率稳定度(全温):±30ppm;")
      (fields
        (field (name "Manufacturer Part") "XSHEELNANF-12MHZ")
        (field (name "Manufacturer") "TAITIEN(泰艺电子)")
      )
      (libsource (lib "easyedapro") (part "XSHEELNANF-12MHZ"))
    )
    (comp (ref "X2")
      (value "32.768kHz")
      (footprint "easyedapro:CRYSTAL-SMD_4P-L8.0-W3.8-BL")
      (description "晶振类型:-;频率:32.768kHz;常温频差:±20ppm;外接负载电容:12.5pF;频率稳定度(全温):-;")
      (fields (field (name "Manufacturer Part") "ABS25-32.768KHZ-T") (field (name "Manufacturer") "ABRACON"))
      (libsource (lib "easyedapro") (part "ABS25-32.768KHZ-T"))
    )
  )
  (nets
    (net (code "1") (name "/74HC_1A") (class "Default")
      (node (ref "U14") (pin "1") (pinfunction "1A_1") (pintype "unspecified"))
      (node (ref "U15") (pin "2") (pinfunction "2_2") (pintype "unspecified"))
    )
    (net (code "2") (name "/74HC_1Y") (class "Default")
      (node (ref "U1") (pin "46") (pinfunction "PB9_46") (pintype "unspecified"))
      (node (ref "U14") (pin "2") (pinfunction "1Y_2") (pintype "unspecified"))
    )
    (net (code "3") (name "/74HC_2A") (class "Default")
      (node (ref "U14") (pin "3") (pinfunction "2A_3") (pintype "unspecified"))
      (node (ref "U15") (pin "3") (pinfunction "3_3") (pintype "unspecified"))
    )
    (net (code "4") (name "/74HC_2Y") (class "Default")
      (node (ref "U1") (pin "29") (pinfunction "PA8_29") (pintype "unspecified"))
      (node (ref "U14") (pin "4") (pinfunction "2Y_4") (pintype "unspecified"))
    )
    (net (code "5") (name "/AOUT1") (class "Default")
      (node (ref "U13") (pin "4") (pinfunction "4_4") (pintype "unspecified"))
      (node (ref "U9") (pin "5") (pinfunction "AOUT1_5") (pintype "unspecified"))
    )
    (net (code "6") (name "/AOUT2") (class "Default")
      (node (ref "U13") (pin "3") (pinfunction "3_3") (pintype "unspecified"))
      (node (ref "U9") (pin "7") (pinfunction "AOUT2_7") (pintype "unspecified"))
    )
    (net (code "7") (name "/BOOT0") (class "Default")
      (node (ref "R10") (pin "2") (pinfunction "2_2") (pintype "input"))
      (node (ref "U1") (pin "44") (pinfunction "BOOT0_44") (pintype "unspecified"))
    )
    (net (code "8") (name "/BOUT1") (class "Default")
      (node (ref "U13") (pin "1") (pinfunction "1_1") (pintype "unspecified"))
      (node (ref "U9") (pin "10") (pinfunction "BOUT1_10") (pintype "unspecified"))
    )
    (net (code "9") (name "/BOUT2") (class "Default")
      (node (ref "U13") (pin "2") (pinfunction "2_2") (pintype "unspecified"))
      (node (ref "U9") (pin "8") (pinfunction "BOUT2_8") (pintype "unspecified"))
    )
    (net (code "10") (name "/D_KU") (class "Default")
      (node (ref "R3") (pin "1") (pinfunction "1_1") (pintype "input"))
      (node (ref "SW3") (pin "1") (pinfunction "1_1") (pintype "unspecified"))
      (node (ref "U1") (pin "18") (pinfunction "PB0_18") (pintype "unspecified"))
    )
    (net (code "11") (name "/ENA") (class "Default")
      (node (ref "U1") (pin "19") (pinfunction "PB1_19") (pintype "unspecified"))
      (node (ref "U9") (pin "21") (pinfunction "NENBL_21") (pintype "unspecified"))
    )
    (net (code "12") (name "/FN_CP") (class "Default")
      (node (ref "R5") (pin "1") (pinfunction "1_1") (pintype "input"))
      (node (ref "SW5") (pin "1") (pinfunction "1_1") (pintype "unspecified"))
      (node (ref "U1") (pin "16") (pinfunction "PA6_16") (pintype "unspecified"))
    )
    (net (code "13") (name "/JTCK") (class "Default")
      (node (ref "U1") (pin "37") (pinfunction "PA14_37") (pintype "unspecified"))
      (node (ref "U5") (pin "2") (pinfunction "2_2") (pintype "unspecified"))
    )
    (net (code "14") (name "/JTMS") (class "Default")
      (node (ref "U1") (pin "34") (pinfunction "PA13_34") (pintype "unspecified"))
      (node (ref "U5") (pin "3") (pinfunction "3_3") (pintype "unspecified"))
    )
    (net (code "15") (name "/KEY_RESET") (class "Default")
      (node (ref "R6") (pin "1") (pinfunction "1_1") (pintype "input"))
      (node (ref "U1") (pin "7") (pinfunction "NRST_7") (pintype "unspecified"))
    )
    (net (code "16") (name "/L_SGSAVE") (class "Default")
      (node (ref "R1") (pin "1") (pinfunction "1_1") (pintype "input"))
      (node (ref "SW1") (pin "1") (pinfunction "1_1") (pintype "unspecified"))
      (node (ref "U1") (pin "15") (pinfunction "PA5_15") (pintype "unspecified"))
    )
    (net (code "17") (name "/MOTRST") (class "Default")
      (node (ref "U1") (pin "27") (pinfunction "PB14_27") (pintype "unspecified"))
      (node (ref "U9") (pin "16") (pinfunction "nRESET_16") (pintype "unspecified"))
      (node (ref "U9") (pin "17") (pinfunction "nSLEEP_17") (pintype "unspecified"))
    )
    (net (code "18") (name "/OSC_IN") (class "Default")
      (node (ref "C1") (pin "2") (pinfunction "2_2") (pintype "input"))
      (node (ref "U1") (pin "5") (pinfunction "PD0-OSC_IN_5") (pintype "unspecified"))
      (node (ref "X1") (pin "1") (pinfunction "OSC1_1") (pintype "input"))
    )
    (net (code "19") (name "/OSC_OUT") (class "Default")
      (node (ref "C7") (pin "2") (pinfunction "2_2") (pintype "input"))
      (node (ref "U1") (pin "6") (pinfunction "PD1-OSC_OUT_6") (pintype "unspecified"))
      (node (ref "X1") (pin "2") (pinfunction "OSC2_2") (pintype "input"))
    )
    (net (code "20") (name "/PA15") (class "Default")
      (node (ref "U1") (pin "38") (pinfunction "PA15_38") (pintype "unspecified"))
      (node (ref "U6") (pin "1") (pinfunction "1_1") (pintype "unspecified"))
    )
    (net (code "21") (name "/PB2") (class "Default")
      (node (ref "U1") (pin "20") (pinfunction "PB2_20") (pintype "unspecified"))
      (node (ref "U6") (pin "2") (pinfunction "2_2") (pintype "unspecified"))
    )
    (net (code "22") (name "/PB3") (class "Default")
      (node (ref "U1") (pin "39") (pinfunction "PB3_39") (pintype "unspecified"))
      (node (ref "U6") (pin "3") (pinfunction "3_3") (pintype "unspecified"))
    )
    (net (code "23") (name "/PB4") (class "Default")
      (node (ref "U1") (pin "40") (pinfunction "PB4_40") (pintype "unspecified"))
      (node (ref "U6") (pin "4") (pinfunction "4_4") (pintype "unspecified"))
    )
    (net (code "24") (name "/PB12") (class "Default")
      (node (ref "U1") (pin "25") (pinfunction "PB12_25") (pintype "unspecified"))
      (node (ref "U6") (pin "5") (pinfunction "5_5") (pintype "unspecified"))
    )
    (net (code "25") (name "/PB15") (class "Default")
      (node (ref "U1") (pin "28") (pinfunction "PB15_28") (pintype "unspecified"))
      (node (ref "U6") (pin "6") (pinfunction "6_6") (pintype "unspecified"))
    )
    (net (code "26") (name "/RS232_RX") (class "Default")
      (node (ref "U18") (pin "13") (pinfunction "R1IN_13") (pintype "unspecified"))
      (node (ref "U19") (pin "3") (pinfunction "3_3") (pintype "unspecified"))
    )
    (net (code "27") (name "/RS232_TX") (class "Default")
      (node (ref "U18") (pin "14") (pinfunction "T1OUT_14") (pintype "unspecified"))
      (node (ref "U19") (pin "2") (pinfunction "2_2") (pintype "unspecified"))
    )
    (net (code "28") (name "/RTC_CE") (class "Default")
      (node (ref "U1") (pin "43") (pinfunction "PB7_43") (pintype "unspecified"))
      (node (ref "U4") (pin "5") (pinfunction "CE_5") (pintype "unspecified"))
    )
    (net (code "29") (name "/RTC_CLK") (class "Default")
      (node (ref "U1") (pin "42") (pinfunction "PB6_42") (pintype "unspecified"))
      (node (ref "U4") (pin "7") (pinfunction "SCLK_7") (pintype "unspecified"))
    )
    (net (code "30") (name "/RTC_IO") (class "Default")
      (node (ref "R9") (pin "1") (pinfunction "1_1") (pintype "input"))
      (node (ref "U1") (pin "41") (pinfunction "PB5_41") (pintype "unspecified"))
      (node (ref "U4") (pin "6") (pinfunction "I/O_6") (pintype "unspecified"))
    )
    (net (code "31") (name "/R_G") (class "Default")
      (node (ref "R4") (pin "1") (pinfunction "1_1") (pintype "input"))
      (node (ref "SW4") (pin "1") (pinfunction "1_1") (pintype "unspecified"))
      (node (ref "U1") (pin "17") (pinfunction "PA7_17") (pintype "unspecified"))
    )
    (net (code "32") (name "/SCL") (class "Default")
      (node (ref "R12") (pin "1") (pinfunction "1_1") (pintype "input"))
      (node (ref "U1") (pin "11") (pinfunction "PA1_11") (pintype "unspecified"))
      (node (ref "U12") (pin "3") (pinfunction "3_3") (pintype "unspecified"))
    )
    (net (code "33") (name "/STEP") (class "Default")
      (node (ref "U1") (pin "45") (pinfunction "PB8_45") (pintype "unspecified"))
      (node (ref "U9") (pin "22") (pinfunction "STEP_22") (pintype "unspecified"))
    )
    (net (code "34") (name "/SWITCH") (class "Default")
      (node (ref "R19") (pin "1") (pinfunction "1_1") (pintype "input"))
      (node (ref "U1") (pin "26") (pinfunction "PB13_26") (pintype "unspecified"))
      (node (ref "U16") (pin "2") (pinfunction "2_2") (pintype "unspecified"))
    )
    (net (code "35") (name "/TEMP_SDA") (class "Default")
      (node (ref "R11") (pin "1") (pinfunction "1_1") (pintype "input"))
      (node (ref "U1") (pin "10") (pinfunction "PA0-WKUP_10") (pintype "unspecified"))
      (node (ref "U12") (pin "4") (pinfunction "4_4") (pintype "unspecified"))
    )
    (net (code "36") (name "/TTL_RX") (class "Default")
      (node (ref "U1") (pin "31") (pinfunction "PA10_31") (pintype "unspecified"))
      (node (ref "U18") (pin "12") (pinfunction "R1OUT_12") (pintype "unspecified"))
    )
    (net (code "37") (name "/TTL_TX") (class "Default")
      (node (ref "U1") (pin "30") (pinfunction "PA9_30") (pintype "unspecified"))
      (node (ref "U18") (pin "11") (pinfunction "T1IN_11") (pintype "unspecified"))
    )
    (net (code "38") (name "/USART2_RX") (class "Default")
      (node (ref "U1") (pin "13") (pinfunction "PA3_13") (pintype "unspecified"))
      (node (ref "U7") (pin "2") (pinfunction "2_2") (pintype "unspecified"))
    )
    (net (code "39") (name "/USART2_TX") (class "Default")
      (node (ref "U1") (pin "12") (pinfunction "PA2_12") (pintype "unspecified"))
      (node (ref "U7") (pin "1") (pinfunction "1_1") (pintype "unspecified"))
    )
    (net (code "40") (name "/USART3_RX") (class "Default")
      (node (ref "FPC1") (pin "6") (pinfunction "6_6") (pintype "unspecified"))
      (node (ref "U1") (pin "22") (pinfunction "PB11_22") (pintype "unspecified"))
    )
    (net (code "41") (name "/USART3_TX") (class "Default")
      (node (ref "FPC1") (pin "5") (pinfunction "5_5") (pintype "unspecified"))
      (node (ref "U1") (pin "21") (pinfunction "PB10_21") (pintype "unspecified"))
    )
    (net (code "42") (name "/USBDM") (class "Default")
      (node (ref "R18") (pin "2") (pinfunction "2_2") (pintype "input"))
      (node (ref "U1") (pin "32") (pinfunction "PA11_32") (pintype "unspecified"))
    )
    (net (code "43") (name "/USBDP") (class "Default")
      (node (ref "R20") (pin "2") (pinfunction "2_2") (pintype "input"))
      (node (ref "R21") (pin "1") (pinfunction "1_1") (pintype "input"))
      (node (ref "U1") (pin "33") (pinfunction "PA12_33") (pintype "unspecified"))
    )
    (net (code "44") (name "/U_SGADJ") (class "Default")
      (node (ref "R2") (pin "1") (pinfunction "1_1") (pintype "input"))
      (node (ref "SW2") (pin "1") (pinfunction "1_1") (pintype "unspecified"))
      (node (ref "U1") (pin "14") (pinfunction "PA4_14") (pintype "unspecified"))
    )
    (net (code "45") (name "/V3P3OUT") (class "Default")
      (node (ref "C20") (pin "2") (pinfunction "2_2") (pintype "unspecified"))
      (node (ref "R16") (pin "1") (pinfunction "1_1") (pintype "unspecified"))
      (node (ref "U9") (pin "15") (pinfunction "V3P3OUT_15") (pintype "unspecified"))
      (node (ref "U9") (pin "24") (pinfunction "MODE0_24") (pintype "unspecified"))
      (node (ref "U9") (pin "25") (pinfunction "MODE1_25") (pintype "unspecified"))
    )
    (net (code "46") (name "3.3V") (class "Default")
      (node (ref "C10") (pin "1") (pinfunction "1_1") (pintype "input"))
      (node (ref "C13") (pin "1") (pinfunction "1_1") (pintype "input"))
      (node (ref "C14") (pin "2") (pinfunction "2_2") (pintype "input"))
      (node (ref "C2") (pin "2") (pinfunction "2_2") (pintype "input"))
      (node (ref "C21") (pin "1") (pinfunction "1_1") (pintype "input"))
      (node (ref "C22") (pin "2") (pinfunction "2_2") (pintype "input"))
      (node (ref "C23") (pin "2") (pinfunction "2_2") (pintype "input"))
      (node (ref "C25") (pin "1") (pinfunction "1_1") (pintype "input"))
      (node (ref "C3") (pin "2") (pinfunction "2_2") (pintype "input"))
      (node (ref "C4") (pin "2") (pinfunction "2_2") (pintype "input"))
      (node (ref "C5") (pin "2") (pinfunction "2_2") (pintype "input"))
      (node (ref "C6") (pin "2") (pinfunction "2_2") (pintype "input"))
      (node (ref "C8") (pin "1") (pinfunction "1_1") (pintype "input"))
      (node (ref "C9") (pin "2") (pinfunction "2_2") (pintype "input"))
      (node (ref "R1") (pin "2") (pinfunction "2_2") (pintype "input"))
      (node (ref "R11") (pin "2") (pinfunction "2_2") (pintype "input"))
      (node (ref "R12") (pin "2") (pinfunction "2_2") (pintype "input"))
      (node (ref "R19") (pin "2") (pinfunction "2_2") (pintype "input"))
      (node (ref "R2") (pin "2") (pinfunction "2_2") (pintype "input"))
      (node (ref "R21") (pin "2") (pinfunction "2_2") (pintype "input"))
      (node (ref "R3") (pin "2") (pinfunction "2_2") (pintype "input"))
      (node (ref "R4") (pin "2") (pinfunction "2_2") (pintype "input"))
      (node (ref "R5") (pin "2") (pinfunction "2_2") (pintype "input"))
      (node (ref "R8") (pin "2") (pinfunction "2_2") (pintype "input"))
      (node (ref "R9") (pin "2") (pinfunction "2_2") (pintype "input"))
      (node (ref "U1") (pin "1") (pinfunction "VBAT_1") (pintype "unspecified"))
      (node (ref "U1") (pin "24") (pinfunction "VDD_1_24") (pintype "unspecified"))
      (node (ref "U1") (pin "36") (pinfunction "VDD_2_36") (pintype "unspecified"))
      (node (ref "U1") (pin "48") (pinfunction "VDD_3_48") (pintype "unspecified"))
      (node (ref "U1") (pin "9") (pinfunction "VDDA_9") (pintype "unspecified"))
      (node (ref "U11") (pin "2") (pinfunction "VOUT(TAB)_2") (pintype "unspecified"))
      (node (ref "U11") (pin "4") (pinfunction "TAB_4") (pintype "unspecified"))
      (node (ref "U12") (pin "1") (pinfunction "1_1") (pintype "unspecified"))
      (node (ref "U14") (pin "14") (pinfunction "VCC_14") (pintype "unspecified"))
      (node (ref "U15") (pin "1") (pinfunction "1_1") (pintype "unspecified"))
      (node (ref "U18") (pin "16") (pinfunction "VCC_16") (pintype "unspecified"))
      (node (ref "U2") (pin "2") (pinfunction "2_2") (pintype "unspecified"))
      (node (ref "U4") (pin "1") (pinfunction "VCC2_1") (pintype "unspecified"))
      (node (ref "U5") (pin "4") (pinfunction "4_4") (pintype "unspecified"))
    )
    (net (code "47") (name "5V") (class "Default")
      (node (ref "C16") (pin "1") (pinfunction "1_1") (pintype "unspecified"))
      (node (ref "C17") (pin "1") (pinfunction "1_1") (pintype "input"))
      (node (ref "FPC1") (pin "1") (pinfunction "1_1") (pintype "unspecified"))
      (node (ref "FPC1") (pin "2") (pinfunction "2_2") (pintype "unspecified"))
      (node (ref "FPC1") (pin "3") (pinfunction "3_3") (pintype "unspecified"))
      (node (ref "L1") (pin "1") (pinfunction "1_1") (pintype "unspecified"))
      (node (ref "U11") (pin "3") (pinfunction "VIN_3") (pintype "unspecified"))
      (node (ref "U3") (pin "1") (pinfunction "1_1") (pintype "input"))
      (node (ref "U8") (pin "3") (pinfunction "FB_3") (pintype "unspecified"))
    )
    (net (code "48") (name "12V") (class "Default")
      (node (ref "C11") (pin "1") (pinfunction "1_1") (pintype "input"))
      (node (ref "C15") (pin "2") (pinfunction "2_2") (pintype "input"))
      (node (ref "C18") (pin "1") (pinfunction "1_1") (pintype "input"))
      (node (ref "C19") (pin "2") (pinfunction "2_2") (pintype "input"))
      (node (ref "CN1") (pin "1") (pinfunction "1_1") (pintype "unspecified"))
      (node (ref "R13") (pin "1") (pinfunction "1_1") (pintype "unspecified"))
      (node (ref "U10") (pin "2") (pinfunction "2_2") (pintype "unspecified"))
      (node (ref "U8") (pin "1") (pinfunction "VIN_1") (pintype "unspecified"))
      (node (ref "U9") (pin "11") (pinfunction "VMB_11") (pintype "unspecified"))
      (node (ref "U9") (pin "4") (pinfunction "VMA_4") (pintype "unspecified"))
    )
    (net (code "49") (name "BATA+") (class "Default")
      (node (ref "B1") (pin "2") (pinfunction "2_2") (pintype "input"))
      (node (ref "U4") (pin "8") (pinfunction "VCC1_8") (pintype "unspecified"))
    )
    (net (code "50") (name "GND") (class "Default")
      (node (ref "B1") (pin "1") (pinfunction "1_1") (pintype "input"))
      (node (ref "C1") (pin "1") (pinfunction "1_1") (pintype "input"))
      (node (ref "C10") (pin "2") (pinfunction "2_2") (pintype "input"))
      (node (ref "C11") (pin "2") (pinfunction "2_2") (pintype "input"))
      (node (ref "C13") (pin "2") (pinfunction "2_2") (pintype "input"))
      (node (ref "C14") (pin "1") (pinfunction "1_1") (pintype "input"))
      (node (ref "C16") (pin "2") (pinfunction "2_2") (pintype "unspecified"))
      (node (ref "C17") (pin "2") (pinfunction "2_2") (pintype "input"))
      (node (ref "C18") (pin "2") (pinfunction "2_2") (pintype "input"))
      (node (ref "C19") (pin "1") (pinfunction "1_1") (pintype "input"))
      (node (ref "C2") (pin "1") (pinfunction "1_1") (pintype "input"))
      (node (ref "C20") (pin "1") (pinfunction "1_1") (pintype "unspecified"))
      (node (ref "C21") (pin "2") (pinfunction "2_2") (pintype "input"))
      (node (ref "C22") (pin "1") (pinfunction "1_1") (pintype "input"))
      (node (ref "C27") (pin "1") (pinfunction "1_1") (pintype "input"))
      (node (ref "C3") (pin "1") (pinfunction "1_1") (pintype "input"))
      (node (ref "C4") (pin "1") (pinfunction "1_1") (pintype "input"))
      (node (ref "C5") (pin "1") (pinfunction "1_1") (pintype "input"))
      (node (ref "C6") (pin "1") (pinfunction "1_1") (pintype "input"))
      (node (ref "C7") (pin "1") (pinfunction "1_1") (pintype "input"))
      (node (ref "C9") (pin "1") (pinfunction "1_1") (pintype "input"))
      (node (ref "CN1") (pin "2") (pinfunction "2_2") (pintype "unspecified"))
      (node (ref "D1") (pin "2") (pinfunction "A_2") (pintype "unspecified"))
      (node (ref "FPC1") (pin "10") (pinfunction "10_10") (pintype "unspecified"))
      (node (ref "FPC1") (pin "11") (pinfunction "11_11") (pintype "unspecified"))
      (node (ref "FPC1") (pin "12") (pinfunction "12_12") (pintype "unspecified"))
      (node (ref "FPC1") (pin "8") (pinfunction "8_8") (pintype "unspecified"))
      (node (ref "FPC1") (pin "9") (pinfunction "9_9") (pintype "unspecified"))
      (node (ref "LED1") (pin "2") (pinfunction "-_2") (pintype "unspecified"))
      (node (ref "R10") (pin "1") (pinfunction "1_1") (pintype "input"))
      (node (ref "R14") (pin "1") (pinfunction "1_1") (pintype "input"))
      (node (ref "R15") (pin "1") (pinfunction "1_1") (pintype "input"))
      (node (ref "R17") (pin "2") (pinfunction "2_2") (pintype "input"))
      (node (ref "R7") (pin "1") (pinfunction "1_1") (pintype "input"))
      (node (ref "SW1") (pin "3") (pinfunction "3_3") (pintype "unspecified"))
      (node (ref "SW2") (pin "3") (pinfunction "3_3") (pintype "unspecified"))
      (node (ref "SW3") (pin "3") (pinfunction "3_3") (pintype "unspecified"))
      (node (ref "SW4") (pin "3") (pinfunction "3_3") (pintype "unspecified"))
      (node (ref "SW5") (pin "3") (pinfunction "3_3") (pintype "unspecified"))
      (node (ref "U1") (pin "23") (pinfunction "VSS_1_23") (pintype "unspecified"))
      (node (ref "U1") (pin "35") (pinfunction "VSS_2_35") (pintype "unspecified"))
      (node (ref "U1") (pin "47") (pinfunction "VSS_3_47") (pintype "unspecified"))
      (node (ref "U1") (pin "8") (pinfunction "VSSA_8") (pintype "unspecified"))
      (node (ref "U10") (pin "1") (pinfunction "1_1") (pintype "unspecified"))
      (node (ref "U11") (pin "1") (pinfunction "ADJ(GND)_1") (pintype "unspecified"))
      (node (ref "U12") (pin "2") (pinfunction "2_2") (pintype "unspecified"))
      (node (ref "U14") (pin "11") (pinfunction "5A_11") (pintype "unspecified"))
      (node (ref "U14") (pin "13") (pinfunction "6A_13") (pintype "unspecified"))
      (node (ref "U14") (pin "5") (pinfunction "3A_5") (pintype "unspecified"))
      (node (ref "U14") (pin "7") (pinfunction "GND_7") (pintype "unspecified"))
      (node (ref "U14") (pin "9") (pinfunction "4A_9") (pintype "unspecified"))
      (node (ref "U15") (pin "4") (pinfunction "4_4") (pintype "unspecified"))
      (node (ref "U16") (pin "1") (pinfunction "1_1") (pintype "unspecified"))
      (node (ref "U17") (pin "1") (pinfunction "1_1") (pintype "unspecified"))
      (node (ref "U19") (pin "1") (pinfunction "1_1") (pintype "unspecified"))
      (node (ref "U3") (pin "2") (pinfunction "2_2") (pintype "input"))
      (node (ref "U4") (pin "4") (pinfunction "GND_4") (pintype "unspecified"))
      (node (ref "U5") (pin "1") (pinfunction "1_1") (pintype "unspecified"))
      (node (ref "U7") (pin "3") (pinfunction "3_3") (pintype "unspecified"))
      (node (ref "U8") (pin "4") (pinfunction "ON/OFF_4") (pintype "unspecified"))
      (node (ref "U8") (pin "5") (pinfunction "GND_5") (pintype "unspecified"))
      (node (ref "U8") (pin "6") (pinfunction "GND_6") (pintype "unspecified"))
      (node (ref "U8") (pin "7") (pinfunction "GND_7") (pintype "unspecified"))
      (node (ref "U8") (pin "8") (pinfunction "GND_8") (pintype "unspecified"))
      (node (ref "U9") (pin "14") (pinfunction "GND_14") (pintype "unspecified"))
      (node (ref "U9") (pin "28") (pinfunction "GND_28") (pintype "unspecified"))
      (node (ref "X2") (pin "2") (pinfunction "GND_2") (pintype "input"))
      (node (ref "X2") (pin "3") (pinfunction "GND_3") (pintype "input"))
    )
    (net (code "51") (name "Net-(C8-Pad2)") (class "Default")
      (node (ref "C8") (pin "2") (pinfunction "2_2") (pintype "input"))
      (node (ref "R6") (pin "2") (pinfunction "2_2") (pintype "input"))
      (node (ref "R7") (pin "2") (pinfunction "2_2") (pintype "input"))
      (node (ref "U2") (pin "1") (pinfunction "1_1") (pintype "unspecified"))
    )
    (net (code "52") (name "Net-(D1-K)") (class "Default")
      (node (ref "D1") (pin "1") (pinfunction "K_1") (pintype "unspecified"))
      (node (ref "L1") (pin "2") (pinfunction "2_2") (pintype "unspecified"))
      (node (ref "U8") (pin "2") (pinfunction "OUT_2") (pintype "unspecified"))
    )
    (net (code "53") (name "Net-(LED1-+)") (class "Default")
      (node (ref "LED1") (pin "1") (pinfunction "+_1") (pintype "unspecified"))
      (node (ref "R8") (pin "1") (pinfunction "1_1") (pintype "input"))
    )
    (net (code "54") (name "Net-(R18-Pad1)") (class "Default")
      (node (ref "R18") (pin "1") (pinfunction "1_1") (pintype "input"))
      (node (ref "U17") (pin "3") (pinfunction "3_3") (pintype "unspecified"))
    )
    (net (code "55") (name "Net-(R20-Pad1)") (class "Default")
      (node (ref "R20") (pin "1") (pinfunction "1_1") (pintype "input"))
      (node (ref "U17") (pin "2") (pinfunction "2_2") (pintype "unspecified"))
    )
    (net (code "56") (name "Net-(U4-X1)") (class "Default")
      (node (ref "U4") (pin "2") (pinfunction "X1_2") (pintype "unspecified"))
      (node (ref "X2") (pin "4") (pinfunction "OUT_4") (pintype "input"))
    )
    (net (code "57") (name "Net-(U4-X2)") (class "Default")
      (node (ref "U4") (pin "3") (pinfunction "X2_3") (pintype "unspecified"))
      (node (ref "X2") (pin "1") (pinfunction "OE#_1") (pintype "input"))
    )
    (net (code "58") (name "Net-(U9-AVREF)") (class "Default")
      (node (ref "R16") (pin "2") (pinfunction "2_2") (pintype "unspecified"))
      (node (ref "R17") (pin "1") (pinfunction "1_1") (pintype "input"))
      (node (ref "U9") (pin "12") (pinfunction "AVREF_12") (pintype "unspecified"))
      (node (ref "U9") (pin "13") (pinfunction "BVREF_13") (pintype "unspecified"))
    )
    (net (code "59") (name "Net-(U9-CP1)") (class "Default")
      (node (ref "C12") (pin "2") (pinfunction "2_2") (pintype "input"))
      (node (ref "U9") (pin "1") (pinfunction "CP1_1") (pintype "unspecified"))
    )
    (net (code "60") (name "Net-(U9-CP2)") (class "Default")
      (node (ref "C12") (pin "1") (pinfunction "1_1") (pintype "input"))
      (node (ref "U9") (pin "2") (pinfunction "CP2_2") (pintype "unspecified"))
    )
    (net (code "61") (name "Net-(U9-ISENA)") (class "Default")
      (node (ref "R14") (pin "2") (pinfunction "2_2") (pintype "input"))
      (node (ref "U9") (pin "6") (pinfunction "ISENA_6") (pintype "unspecified"))
    )
    (net (code "62") (name "Net-(U9-ISENB)") (class "Default")
      (node (ref "R15") (pin "2") (pinfunction "2_2") (pintype "input"))
      (node (ref "U9") (pin "9") (pinfunction "ISENB_9") (pintype "unspecified"))
    )
    (net (code "63") (name "Net-(U9-VCP)") (class "Default")
      (node (ref "C15") (pin "1") (pinfunction "1_1") (pintype "input"))
      (node (ref "R13") (pin "2") (pinfunction "2_2") (pintype "unspecified"))
      (node (ref "U9") (pin "3") (pinfunction "VCP_3") (pintype "unspecified"))
    )
    (net (code "64") (name "Net-(U18-C1+)") (class "Default")
      (node (ref "C24") (pin "2") (pinfunction "2_2") (pintype "input"))
      (node (ref "U18") (pin "1") (pinfunction "C1+_1") (pintype "unspecified"))
    )
    (net (code "65") (name "Net-(U18-C1-)") (class "Default")
      (node (ref "C24") (pin "1") (pinfunction "1_1") (pintype "input"))
      (node (ref "U18") (pin "3") (pinfunction "C1-_3") (pintype "unspecified"))
    )
    (net (code "66") (name "Net-(U18-C2+)") (class "Default")
      (node (ref "C26") (pin "2") (pinfunction "2_2") (pintype "input"))
      (node (ref "U18") (pin "4") (pinfunction "C2+_4") (pintype "unspecified"))
    )
    (net (code "67") (name "Net-(U18-C2-)") (class "Default")
      (node (ref "C26") (pin "1") (pinfunction "1_1") (pintype "input"))
      (node (ref "U18") (pin "5") (pinfunction "C2-_5") (pintype "unspecified"))
    )
    (net (code "68") (name "Net-(U18-GND)") (class "Default")
      (node (ref "C25") (pin "2") (pinfunction "2_2") (pintype "input"))
      (node (ref "U18") (pin "15") (pinfunction "GND_15") (pintype "unspecified"))
    )
    (net (code "69") (name "Net-(U18-V+)") (class "Default")
      (node (ref "C23") (pin "1") (pinfunction "1_1") (pintype "input"))
      (node (ref "U18") (pin "2") (pinfunction "V+_2") (pintype "unspecified"))
    )
    (net (code "70") (name "Net-(U18-V-)") (class "Default")
      (node (ref "C27") (pin "2") (pinfunction "2_2") (pintype "input"))
      (node (ref "U18") (pin "6") (pinfunction "V-_6") (pintype "unspecified"))
    )
    (net (code "71") (name "unconnected-(FPC1-Pad4)") (class "Default")
      (node (ref "FPC1") (pin "4") (pinfunction "4_4") (pintype "unspecified+no_connect"))
    )
    (net (code "72") (name "unconnected-(FPC1-Pad7)") (class "Default")
      (node (ref "FPC1") (pin "7") (pinfunction "7_7") (pintype "unspecified+no_connect"))
    )
    (net (code "73") (name "unconnected-(SW1-Pad2)") (class "Default")
      (node (ref "SW1") (pin "2") (pinfunction "2_2") (pintype "unspecified+no_connect"))
    )
    (net (code "74") (name "unconnected-(SW1-Pad4)") (class "Default")
      (node (ref "SW1") (pin "4") (pinfunction "4_4") (pintype "unspecified+no_connect"))
    )
    (net (code "75") (name "unconnected-(SW2-Pad2)") (class "Default")
      (node (ref "SW2") (pin "2") (pinfunction "2_2") (pintype "unspecified+no_connect"))
    )
    (net (code "76") (name "unconnected-(SW2-Pad4)") (class "Default")
      (node (ref "SW2") (pin "4") (pinfunction "4_4") (pintype "unspecified+no_connect"))
    )
    (net (code "77") (name "unconnected-(SW3-Pad2)") (class "Default")
      (node (ref "SW3") (pin "2") (pinfunction "2_2") (pintype "unspecified+no_connect"))
    )
    (net (code "78") (name "unconnected-(SW3-Pad4)") (class "Default")
      (node (ref "SW3") (pin "4") (pinfunction "4_4") (pintype "unspecified+no_connect"))
    )
    (net (code "79") (name "unconnected-(SW4-Pad2)") (class "Default")
      (node (ref "SW4") (pin "2") (pinfunction "2_2") (pintype "unspecified+no_connect"))
    )
    (net (code "80") (name "unconnected-(SW4-Pad4)") (class "Default")
      (node (ref "SW4") (pin "4") (pinfunction "4_4") (pintype "unspecified+no_connect"))
    )
    (net (code "81") (name "unconnected-(SW5-Pad2)") (class "Default")
      (node (ref "SW5") (pin "2") (pinfunction "2_2") (pintype "unspecified+no_connect"))
    )
    (net (code "82") (name "unconnected-(SW5-Pad4)") (class "Default")
      (node (ref "SW5") (pin "4") (pinfunction "4_4") (pintype "unspecified+no_connect"))
    )
    (net (code "83") (name "unconnected-(U1-PC13-TAMPER-RTC-Pad2)") (class "Default")
      (node (ref "U1") (pin "2") (pinfunction "PC13-TAMPER-RTC_2") (pintype "unspecified+no_connect"))
    )
    (net (code "84") (name "unconnected-(U1-PC14-OSC32_IN-Pad3)") (class "Default")
      (node (ref "U1") (pin "3") (pinfunction "PC14-OSC32_IN_3") (pintype "unspecified+no_connect"))
    )
    (net (code "85") (name "unconnected-(U1-PC15-OSC32_OUT-Pad4)") (class "Default")
      (node (ref "U1") (pin "4") (pinfunction "PC15-OSC32_OUT_4") (pintype "unspecified+no_connect"))
    )
    (net (code "86") (name "unconnected-(U9-DECAY-Pad19)") (class "Default")
      (node (ref "U9") (pin "19") (pinfunction "DECAY_19") (pintype "unspecified+no_connect"))
    )
    (net (code "87") (name "unconnected-(U9-DIR-Pad20)") (class "Default")
      (node (ref "U9") (pin "20") (pinfunction "DIR_20") (pintype "unspecified+no_connect"))
    )
    (net (code "88") (name "unconnected-(U9-EP-Pad29)") (class "Default")
      (node (ref "U9") (pin "29") (pinfunction "EP_29") (pintype "unspecified+no_connect"))
    )
    (net (code "89") (name "unconnected-(U9-MODE2-Pad26)") (class "Default")
      (node (ref "U9") (pin "26") (pinfunction "MODE2_26") (pintype "unspecified+no_connect"))
    )
    (net (code "90") (name "unconnected-(U9-NC-Pad23)") (class "Default")
      (node (ref "U9") (pin "23") (pinfunction "NC_23") (pintype "unspecified+no_connect"))
    )
    (net (code "91") (name "unconnected-(U9-nFAULT-Pad18)") (class "Default")
      (node (ref "U9") (pin "18") (pinfunction "nFAULT_18") (pintype "unspecified+no_connect"))
    )
    (net (code "92") (name "unconnected-(U9-nHOME-Pad27)") (class "Default")
      (node (ref "U9") (pin "27") (pinfunction "nHOME_27") (pintype "unspecified+no_connect"))
    )
    (net (code "93") (name "unconnected-(U14-3Y-Pad6)") (class "Default")
      (node (ref "U14") (pin "6") (pinfunction "3Y_6") (pintype "unspecified+no_connect"))
    )
    (net (code "94") (name "unconnected-(U14-4Y-Pad8)") (class "Default")
      (node (ref "U14") (pin "8") (pinfunction "4Y_8") (pintype "unspecified+no_connect"))
    )
    (net (code "95") (name "unconnected-(U14-5Y-Pad10)") (class "Default")
      (node (ref "U14") (pin "10") (pinfunction "5Y_10") (pintype "unspecified+no_connect"))
    )
    (net (code "96") (name "unconnected-(U14-6Y-Pad12)") (class "Default")
      (node (ref "U14") (pin "12") (pinfunction "6Y_12") (pintype "unspecified+no_connect"))
    )
    (net (code "97") (name "unconnected-(U18-R2IN-Pad8)") (class "Default")
      (node (ref "U18") (pin "8") (pinfunction "R2IN_8") (pintype "unspecified+no_connect"))
    )
    (net (code "98") (name "unconnected-(U18-R2OUT-Pad9)") (class "Default")
      (node (ref "U18") (pin "9") (pinfunction "R2OUT_9") (pintype "unspecified+no_connect"))
    )
    (net (code "99") (name "unconnected-(U18-T2IN-Pad10)") (class "Default")
      (node (ref "U18") (pin "10") (pinfunction "T2IN_10") (pintype "unspecified+no_connect"))
    )
    (net (code "100") (name "unconnected-(U18-T2OUT-Pad7)") (class "Default")
      (node (ref "U18") (pin "7") (pinfunction "T2OUT_7") (pintype "unspecified+no_connect"))
    )
    (net (code "101") (name "unconnected-(U20-Pad1)") (class "Default")
      (node (ref "U20") (pin "1") (pinfunction "1_1") (pintype "unspecified+no_connect"))
    )
    (net (code "102") (name "unconnected-(U21-Pad1)") (class "Default")
      (node (ref "U21") (pin "1") (pinfunction "1_1") (pintype "unspecified+no_connect"))
    )
    (net (code "103") (name "unconnected-(U22-Pad1)") (class "Default")
      (node (ref "U22") (pin "1") (pinfunction "1_1") (pintype "unspecified+no_connect"))
    )
    (net (code "104") (name "unconnected-(U23-Pad1)") (class "Default")
      (node (ref "U23") (pin "1") (pinfunction "1_1") (pintype "unspecified+no_connect"))
    )
  )
)
